# Sheet1.net
KiCad netlist of a schematic drawn in Altium Designer
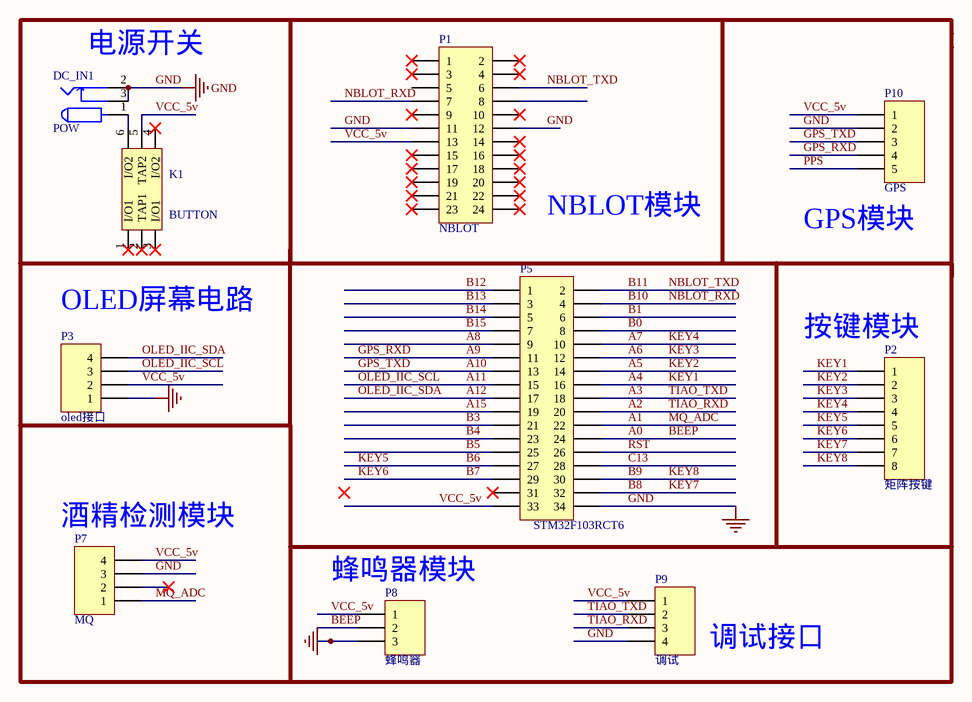
[diagram p0: Sheet1.SchDoc]

(export (version "E")
  (design (tool "Eeschema 10.0.6"))
  (components
    (comp (ref "DC_IN1") (value "POW") (footprint "DC10B") (libsource (lib "STM32F103") (part "POW")))
    (comp (ref "K1") (value "BUTTON") (footprint "BTN8.5*8.5") (libsource (lib "STM32F103") (part "BUTTON")))
    (comp (ref "P1")
      (value "NBLOT")
      (footprint "NBLOT")
      (description "Header, 12-Pin, Dual row")
      (fields (field (name "PUBLISHER") "Altium Limited"))
      (libsource (lib "Miscellaneous Connectors") (part "Header 12X2"))
    )
    (comp (ref "P2")
      (value "矩阵按键")
      (footprint "HDR1X8")
      (description "Header, 8-Pin")
      (fields (field (name "PUBLISHER") "Altium Limited"))
      (libsource (lib "Miscellaneous Connectors") (part "Header 8"))
    )
    (comp (ref "P3")
      (value "oled接口")
      (footprint "HDR1X4")
      (description "Header, 4-Pin")
      (fields (field (name "PUBLISHER") "Altium Limited"))
      (libsource (lib "Miscellaneous Connectors") (part "Header 4"))
    )
    (comp (ref "P5")
      (value "STM32F103RCT6")
      (footprint "stm32最小系统")
      (description "Header, 17-Pin, Dual row")
      (fields (field (name "PUBLISHER") "Altium Limited"))
      (libsource (lib "Miscellaneous Connectors") (part "Header 17X2"))
    )
    (comp (ref "P7")
      (value "MQ")
      (footprint "HDR1X4")
      (description "Header, 4-Pin")
      (fields (field (name "PUBLISHER") "Altium Limited"))
      (libsource (lib "Miscellaneous Connectors") (part "Header 4"))
    )
    (comp (ref "P8")
      (value "蜂鸣器")
      (footprint "HDR1X3")
      (description "Header, 3-Pin")
      (fields (field (name "PUBLISHER") "Altium Limited"))
      (libsource (lib "Miscellaneous Connectors") (part "Header 3"))
    )
    (comp (ref "P9")
      (value "调试")
      (footprint "HDR1X4")
      (description "Header, 4-Pin")
      (fields (field (name "PUBLISHER") "Altium Limited"))
      (libsource (lib "") (part "Header 4_1"))
    )
    (comp (ref "P10")
      (value "GPS")
      (footprint "HDR1X5")
      (description "Header, 5-Pin")
      (fields (field (name "PUBLISHER") "Altium Limited"))
      (libsource (lib "Miscellaneous Connectors") (part "Header 5"))
    )
  )
  (nets
    (net (code "1") (name "/A0") (class "Default")
      (node (ref "P5") (pin "24") (pinfunction "24_24") (pintype "passive"))
      (node (ref "P8") (pin "2") (pinfunction "2_2") (pintype "passive"))
    )
    (net (code "2") (name "/A1") (class "Default")
      (node (ref "P5") (pin "22") (pinfunction "22_22") (pintype "passive"))
      (node (ref "P7") (pin "1") (pinfunction "1_1") (pintype "passive"))
    )
    (net (code "3") (name "/A2") (class "Default")
      (node (ref "P5") (pin "20") (pinfunction "20_20") (pintype "passive"))
      (node (ref "P9") (pin "3") (pinfunction "3_3") (pintype "passive"))
    )
    (net (code "4") (name "/A3") (class "Default")
      (node (ref "P5") (pin "18") (pinfunction "18_18") (pintype "passive"))
      (node (ref "P9") (pin "2") (pinfunction "2_2") (pintype "passive"))
    )
    (net (code "5") (name "/A4") (class "Default")
      (node (ref "P2") (pin "1") (pinfunction "1_1") (pintype "passive"))
      (node (ref "P5") (pin "16") (pinfunction "16_16") (pintype "passive"))
    )
    (net (code "6") (name "/A5") (class "Default")
      (node (ref "P2") (pin "2") (pinfunction "2_2") (pintype "passive"))
      (node (ref "P5") (pin "14") (pinfunction "14_14") (pintype "passive"))
    )
    (net (code "7") (name "/A6") (class "Default")
      (node (ref "P2") (pin "3") (pinfunction "3_3") (pintype "passive"))
      (node (ref "P5") (pin "12") (pinfunction "12_12") (pintype "passive"))
    )
    (net (code "8") (name "/A7") (class "Default")
      (node (ref "P2") (pin "4") (pinfunction "4_4") (pintype "passive"))
      (node (ref "P5") (pin "10") (pinfunction "10_10") (pintype "passive"))
    )
    (net (code "9") (name "/A8") (class "Default")
      (node (ref "P5") (pin "9") (pinfunction "9_9") (pintype "passive"))
    )
    (net (code "10") (name "/A9") (class "Default")
      (node (ref "P10") (pin "4") (pinfunction "4_4") (pintype "passive"))
      (node (ref "P5") (pin "11") (pinfunction "11_11") (pintype "passive"))
    )
    (net (code "11") (name "/A10") (class "Default")
      (node (ref "P10") (pin "3") (pinfunction "3_3") (pintype "passive"))
      (node (ref "P5") (pin "13") (pinfunction "13_13") (pintype "passive"))
    )
    (net (code "12") (name "/A11") (class "Default")
      (node (ref "P3") (pin "3") (pinfunction "3_3") (pintype "passive"))
      (node (ref "P5") (pin "15") (pinfunction "15_15") (pintype "passive"))
    )
    (net (code "13") (name "/A12") (class "Default")
      (node (ref "P3") (pin "4") (pinfunction "4_4") (pintype "passive"))
      (node (ref "P5") (pin "17") (pinfunction "17_17") (pintype "passive"))
    )
    (net (code "14") (name "/A15") (class "Default")
      (node (ref "P5") (pin "19") (pinfunction "19_19") (pintype "passive"))
    )
    (net (code "15") (name "/B0") (class "Default")
      (node (ref "P5") (pin "8") (pinfunction "8_8") (pintype "passive"))
    )
    (net (code "16") (name "/B1") (class "Default")
      (node (ref "P5") (pin "6") (pinfunction "6_6") (pintype "passive"))
    )
    (net (code "17") (name "/B3") (class "Default")
      (node (ref "P5") (pin "21") (pinfunction "21_21") (pintype "passive"))
    )
    (net (code "18") (name "/B4") (class "Default")
      (node (ref "P5") (pin "23") (pinfunction "23_23") (pintype "passive"))
    )
    (net (code "19") (name "/B5") (class "Default")
      (node (ref "P5") (pin "25") (pinfunction "25_25") (pintype "passive"))
    )
    (net (code "20") (name "/B6") (class "Default")
      (node (ref "P2") (pin "5") (pinfunction "5_5") (pintype "passive"))
      (node (ref "P5") (pin "27") (pinfunction "27_27") (pintype "passive"))
    )
    (net (code "21") (name "/B7") (class "Default")
      (node (ref "P2") (pin "6") (pinfunction "6_6") (pintype "passive"))
      (node (ref "P5") (pin "29") (pinfunction "29_29") (pintype "passive"))
    )
    (net (code "22") (name "/B8") (class "Default")
      (node (ref "P2") (pin "7") (pinfunction "7_7") (pintype "passive"))
      (node (ref "P5") (pin "32") (pinfunction "32_32") (pintype "passive"))
    )
    (net (code "23") (name "/B9") (class "Default")
      (node (ref "P2") (pin "8") (pinfunction "8_8") (pintype "passive"))
      (node (ref "P5") (pin "30") (pinfunction "30_30") (pintype "passive"))
    )
    (net (code "24") (name "/B10") (class "Default")
      (node (ref "P1") (pin "7") (pinfunction "7_7") (pintype "passive"))
      (node (ref "P5") (pin "4") (pinfunction "4_4") (pintype "passive"))
    )
    (net (code "25") (name "/B11") (class "Default")
      (node (ref "P1") (pin "6") (pinfunction "6_6") (pintype "passive"))
      (node (ref "P5") (pin "2") (pinfunction "2_2") (pintype "passive"))
    )
    (net (code "26") (name "/B12") (class "Default")
      (node (ref "P5") (pin "1") (pinfunction "1_1") (pintype "passive"))
    )
    (net (code "27") (name "/B13") (class "Default")
      (node (ref "P5") (pin "3") (pinfunction "3_3") (pintype "passive"))
    )
    (net (code "28") (name "/B14") (class "Default")
      (node (ref "P5") (pin "5") (pinfunction "5_5") (pintype "passive"))
    )
    (net (code "29") (name "/B15") (class "Default")
      (node (ref "P5") (pin "7") (pinfunction "7_7") (pintype "passive"))
    )
    (net (code "30") (name "/C13") (class "Default")
      (node (ref "P5") (pin "28") (pinfunction "28_28") (pintype "passive"))
    )
    (net (code "31") (name "/PPS") (class "Default")
      (node (ref "P10") (pin "5") (pinfunction "5_5") (pintype "passive"))
    )
    (net (code "32") (name "/RST") (class "Default")
      (node (ref "P5") (pin "26") (pinfunction "26_26") (pintype "passive"))
    )
    (net (code "33") (name "/VCC_5v") (class "Default")
      (node (ref "K1") (pin "5") (pinfunction "TAP2_5") (pintype "passive"))
      (node (ref "P1") (pin "13") (pinfunction "13_13") (pintype "passive"))
      (node (ref "P10") (pin "1") (pinfunction "1_1") (pintype "passive"))
      (node (ref "P3") (pin "2") (pinfunction "2_2") (pintype "passive"))
      (node (ref "P5") (pin "33") (pinfunction "33_33") (pintype "passive"))
      (node (ref "P7") (pin "4") (pinfunction "4_4") (pintype "passive"))
      (node (ref "P8") (pin "1") (pinfunction "1_1") (pintype "passive"))
      (node (ref "P9") (pin "1") (pinfunction "1_1") (pintype "passive"))
    )
    (net (code "34") (name "GND") (class "Default")
      (node (ref "DC_IN1") (pin "2") (pintype "passive"))
      (node (ref "DC_IN1") (pin "3") (pintype "passive"))
      (node (ref "P1") (pin "11") (pinfunction "11_11") (pintype "passive"))
      (node (ref "P1") (pin "12") (pinfunction "12_12") (pintype "passive"))
      (node (ref "P10") (pin "2") (pinfunction "2_2") (pintype "passive"))
      (node (ref "P3") (pin "1") (pinfunction "1_1") (pintype "passive"))
      (node (ref "P5") (pin "34") (pinfunction "34_34") (pintype "passive"))
      (node (ref "P7") (pin "3") (pinfunction "3_3") (pintype "passive"))
      (node (ref "P8") (pin "3") (pinfunction "3_3") (pintype "passive"))
      (node (ref "P9") (pin "4") (pinfunction "4_4") (pintype "passive"))
    )
    (net (code "35") (name "Net-(DC_IN1-Pad1)") (class "Default")
      (node (ref "DC_IN1") (pin "1") (pintype "passive"))
      (node (ref "K1") (pin "6") (pinfunction "I/O2_6") (pintype "passive"))
    )
    (net (code "36") (name "unconnected-(K1-I{slash}O1-Pad1)") (class "Default")
      (node (ref "K1") (pin "1") (pinfunction "I/O1_1") (pintype "passive+no_connect"))
    )
    (net (code "37") (name "unconnected-(K1-I{slash}O1-Pad3)") (class "Default")
      (node (ref "K1") (pin "3") (pinfunction "I/O1_3") (pintype "passive+no_connect"))
    )
    (net (code "38") (name "unconnected-(K1-I{slash}O2-Pad4)") (class "Default")
      (node (ref "K1") (pin "4") (pinfunction "I/O2_4") (pintype "passive+no_connect"))
    )
    (net (code "39") (name "unconnected-(K1-TAP1-Pad2)") (class "Default")
      (node (ref "K1") (pin "2") (pinfunction "TAP1_2") (pintype "passive+no_connect"))
    )
    (net (code "40") (name "unconnected-(P1-Pad1)") (class "Default")
      (node (ref "P1") (pin "1") (pinfunction "1_1") (pintype "passive+no_connect"))
    )
    (net (code "41") (name "unconnected-(P1-Pad2)") (class "Default")
      (node (ref "P1") (pin "2") (pinfunction "2_2") (pintype "passive+no_connect"))
    )
    (net (code "42") (name "unconnected-(P1-Pad3)") (class "Default")
      (node (ref "P1") (pin "3") (pinfunction "3_3") (pintype "passive+no_connect"))
    )
    (net (code "43") (name "unconnected-(P1-Pad4)") (class "Default")
      (node (ref "P1") (pin "4") (pinfunction "4_4") (pintype "passive+no_connect"))
    )
    (net (code "44") (name "unconnected-(P1-Pad5)") (class "Default")
      (node (ref "P1") (pin "5") (pinfunction "5_5") (pintype "passive"))
    )
    (net (code "45") (name "unconnected-(P1-Pad8)") (class "Default")
      (node (ref "P1") (pin "8") (pinfunction "8_8") (pintype "passive"))
    )
    (net (code "46") (name "unconnected-(P1-Pad9)") (class "Default")
      (node (ref "P1") (pin "9") (pinfunction "9_9") (pintype "passive+no_connect"))
    )
    (net (code "47") (name "unconnected-(P1-Pad10)") (class "Default")
      (node (ref "P1") (pin "10") (pinfunction "10_10") (pintype "passive+no_connect"))
    )
    (net (code "48") (name "unconnected-(P1-Pad14)") (class "Default")
      (node (ref "P1") (pin "14") (pinfunction "14_14") (pintype "passive+no_connect"))
    )
    (net (code "49") (name "unconnected-(P1-Pad15)") (class "Default")
      (node (ref "P1") (pin "15") (pinfunction "15_15") (pintype "passive+no_connect"))
    )
    (net (code "50") (name "unconnected-(P1-Pad16)") (class "Default")
      (node (ref "P1") (pin "16") (pinfunction "16_16") (pintype "passive+no_connect"))
    )
    (net (code "51") (name "unconnected-(P1-Pad17)") (class "Default")
      (node (ref "P1") (pin "17") (pinfunction "17_17") (pintype "passive+no_connect"))
    )
    (net (code "52") (name "unconnected-(P1-Pad18)") (class "Default")
      (node (ref "P1") (pin "18") (pinfunction "18_18") (pintype "passive+no_connect"))
    )
    (net (code "53") (name "unconnected-(P1-Pad19)") (class "Default")
      (node (ref "P1") (pin "19") (pinfunction "19_19") (pintype "passive+no_connect"))
    )
    (net (code "54") (name "unconnected-(P1-Pad20)") (class "Default")
      (node (ref "P1") (pin "20") (pinfunction "20_20") (pintype "passive+no_connect"))
    )
    (net (code "55") (name "unconnected-(P1-Pad21)") (class "Default")
      (node (ref "P1") (pin "21") (pinfunction "21_21") (pintype "passive+no_connect"))
    )
    (net (code "56") (name "unconnected-(P1-Pad22)") (class "Default")
      (node (ref "P1") (pin "22") (pinfunction "22_22") (pintype "passive+no_connect"))
    )
    (net (code "57") (name "unconnected-(P1-Pad23)") (class "Default")
      (node (ref "P1") (pin "23") (pinfunction "23_23") (pintype "passive+no_connect"))
    )
    (net (code "58") (name "unconnected-(P1-Pad24)") (class "Default")
      (node (ref "P1") (pin "24") (pinfunction "24_24") (pintype "passive+no_connect"))
    )
    (net (code "59") (name "unconnected-(P5-Pad31)") (class "Default")
      (node (ref "P5") (pin "31") (pinfunction "31_31") (pintype "passive+no_connect"))
    )
    (net (code "60") (name "unconnected-(P7-Pad2)") (class "Default")
      (node (ref "P7") (pin "2") (pinfunction "2_2") (pintype "passive+no_connect"))
    )
  )
)
